# IOTBeev0_1.net
KiCad netlist of a schematic drawn in EAGLE
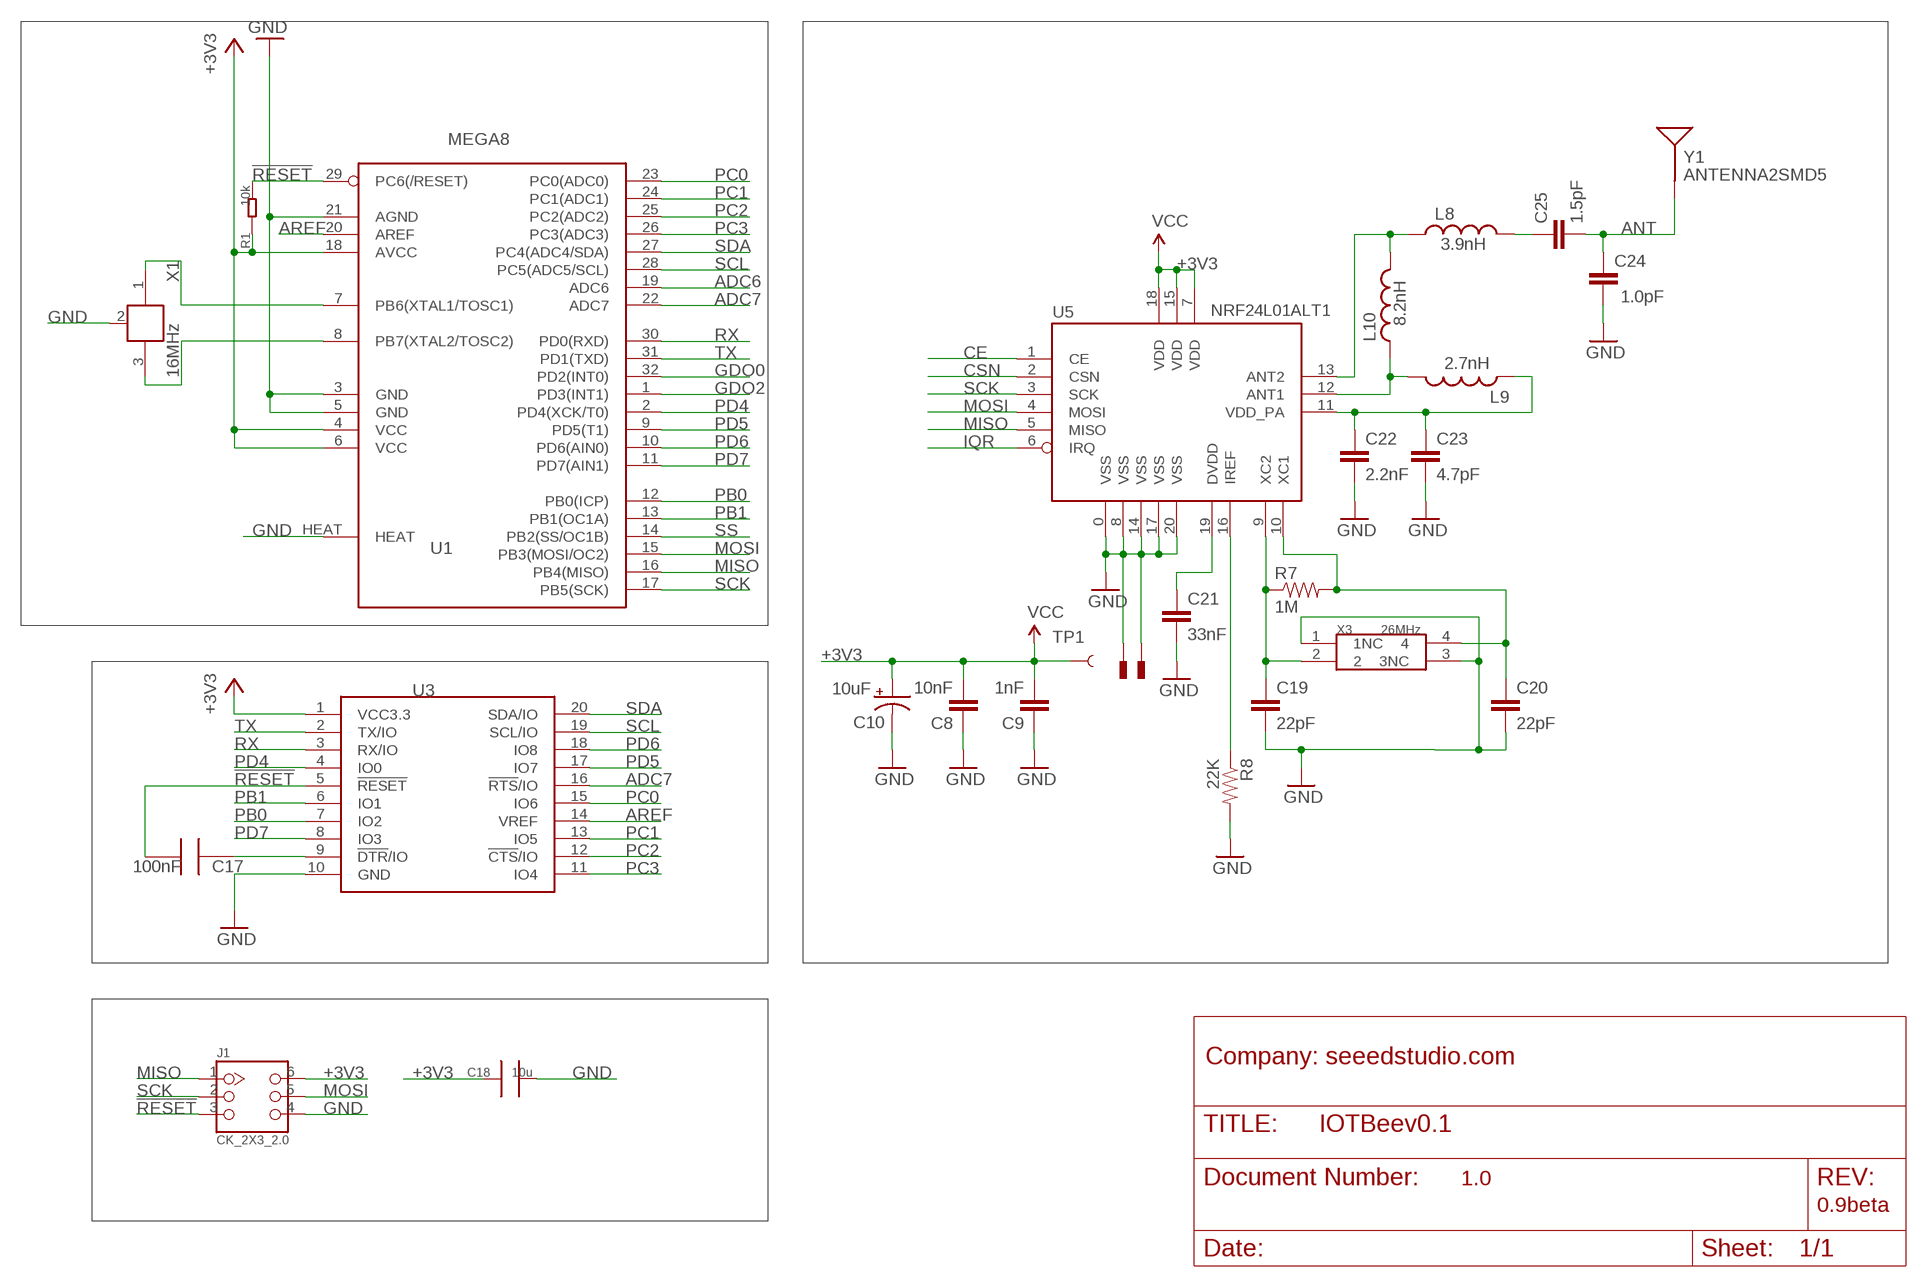
[diagram p0: schematic, sheet 1]

(export (version "E")
  (design (tool "Eeschema 10.0.6"))
  (components
    (comp (ref "C8")
      (value "10nF")
      (footprint "eagle-import:0402-CAP")
      (libsource (lib "eagle-import") (part "CAP0402-CAP"))
    )
    (comp (ref "C9")
      (value "1nF")
      (footprint "eagle-import:0402-CAP")
      (libsource (lib "eagle-import") (part "CAP0402-CAP"))
    )
    (comp (ref "C10")
      (value "10uF")
      (footprint "eagle-import:EIA3528")
      (libsource (lib "eagle-import") (part "CAP_POL3528"))
    )
    (comp (ref "C17")
      (value "100nF")
      (footprint "eagle-import:0603_S")
      (libsource (lib "eagle-import") (part "C0603_S"))
    )
    (comp (ref "C18")
      (value "10u")
      (footprint "eagle-import:0805")
      (libsource (lib "eagle-import") (part "C0805"))
    )
    (comp (ref "C19")
      (value "22pF")
      (footprint "eagle-import:0402-CAP")
      (libsource (lib "eagle-import") (part "CAP0402-CAP"))
    )
    (comp (ref "C20")
      (value "22pF")
      (footprint "eagle-import:0402-CAP")
      (libsource (lib "eagle-import") (part "CAP0402-CAP"))
    )
    (comp (ref "C21")
      (value "33nF")
      (footprint "eagle-import:0402-CAP")
      (libsource (lib "eagle-import") (part "CAP0402-CAP"))
    )
    (comp (ref "C22")
      (value "2.2nF")
      (footprint "eagle-import:0402-CAP")
      (libsource (lib "eagle-import") (part "CAP0402-CAP"))
    )
    (comp (ref "C23")
      (value "4.7pF")
      (footprint "eagle-import:0402-CAP")
      (libsource (lib "eagle-import") (part "CAP0402-CAP"))
    )
    (comp (ref "C24")
      (value "1.0pF")
      (footprint "eagle-import:0402-CAP")
      (libsource (lib "eagle-import") (part "CAP0402-CAP"))
    )
    (comp (ref "C25")
      (value "1.5pF")
      (footprint "eagle-import:0402-CAP")
      (libsource (lib "eagle-import") (part "CAP0402-CAP"))
    )
    (comp (ref "J1")
      (value "CK_2X3_2.0")
      (footprint "eagle-import:CK_2X3_2.0")
      (libsource (lib "eagle-import") (part "CK_2X3_2.0"))
    )
    (comp (ref "L8")
      (value "3.9nH")
      (footprint "eagle-import:C0402")
      (libsource (lib "eagle-import") (part "INDUCTOR0402"))
    )
    (comp (ref "L9")
      (value "2.7nH")
      (footprint "eagle-import:C0402")
      (libsource (lib "eagle-import") (part "INDUCTOR0402"))
    )
    (comp (ref "L10")
      (value "8.2nH")
      (footprint "eagle-import:C0402")
      (libsource (lib "eagle-import") (part "INDUCTOR0402"))
    )
    (comp (ref "R1")
      (value "10k")
      (footprint "eagle-import:0603_S")
      (libsource (lib "eagle-import") (part "R0603_S"))
    )
    (comp (ref "R7")
      (value "1M")
      (footprint "eagle-import:0402-RES")
      (libsource (lib "eagle-import") (part "RESISTOR0402-RES"))
    )
    (comp (ref "R8")
      (value "22K")
      (footprint "eagle-import:0402-RES")
      (libsource (lib "eagle-import") (part "RESISTOR0402-RES"))
    )
    (comp (ref "TP1")
      (value "TEST-POINT3X5")
      (footprint "eagle-import:PAD.03X.05")
      (libsource (lib "eagle-import") (part "TEST-POINT3X5"))
    )
    (comp (ref "U$2")
      (value "PAD")
      (footprint "eagle-import:PAD-0.008")
      (libsource (lib "eagle-import") (part "PAD"))
    )
    (comp (ref "U$4")
      (value "PAD")
      (footprint "eagle-import:PAD-0.008")
      (libsource (lib "eagle-import") (part "PAD"))
    )
    (comp (ref "U1")
      (value "MEGA8")
      (footprint "eagle-import:MLF32X")
      (libsource (lib "eagle-import") (part "MEGA8"))
    )
    (comp (ref "U3")
      (value "BEE-OPENBEE-BTSMD")
      (footprint "eagle-import:20P-SMD-2.0-BT")
      (libsource (lib "eagle-import") (part "BEE-OPENBEE-BTSMD"))
    )
    (comp (ref "U5")
      (value "NRF24L01ALT1")
      (footprint "eagle-import:QFN20_ALT1")
      (libsource (lib "eagle-import") (part "NRF24L01ALT1"))
    )
    (comp (ref "X1")
      (value "16MHz")
      (footprint "eagle-import:XTAL_3X2")
      (libsource (lib "eagle-import") (part "XTAL_NCVER"))
    )
    (comp (ref "X3")
      (value "26MHz")
      (footprint "eagle-import:X3225")
      (libsource (lib "eagle-import") (part "XTAL_SMD_3225"))
    )
    (comp (ref "Y1")
      (value "ANTENNA2SMD5")
      (footprint "eagle-import:ANTENNA-CHIP5")
      (libsource (lib "eagle-import") (part "ANTENNA2SMD5"))
    )
  )
  (nets
    (net (code "1") (name "+3V3") (class "Default")
      (node (ref "C10") (pin "A") (pinfunction "+_A") (pintype "passive"))
      (node (ref "C18") (pin "1") (pinfunction "1_1") (pintype "bidirectional"))
      (node (ref "C8") (pin "2") (pinfunction "2_2") (pintype "passive"))
      (node (ref "C9") (pin "2") (pinfunction "2_2") (pintype "passive"))
      (node (ref "J1") (pin "6") (pinfunction "P$6_6") (pintype "bidirectional"))
      (node (ref "R1") (pin "1") (pinfunction "1_1") (pintype "bidirectional"))
      (node (ref "TP1") (pin "P$1") (pinfunction "1_P$1") (pintype "bidirectional"))
      (node (ref "U1") (pin "18") (pinfunction "AVCC_18") (pintype "bidirectional"))
      (node (ref "U1") (pin "4") (pinfunction "VCC_4") (pintype "bidirectional"))
      (node (ref "U1") (pin "6") (pinfunction "VCC_6") (pintype "bidirectional"))
      (node (ref "U3") (pin "1") (pinfunction "VCC3.3_1") (pintype "bidirectional"))
      (node (ref "U5") (pin "15") (pinfunction "VDD_15") (pintype "power_in"))
      (node (ref "U5") (pin "18") (pinfunction "VDD_18") (pintype "power_in"))
      (node (ref "U5") (pin "7") (pinfunction "VDD_7") (pintype "power_in"))
    )
    (net (code "2") (name "/ADC6") (class "Default")
      (node (ref "U1") (pin "19") (pinfunction "ADC6_19") (pintype "bidirectional"))
    )
    (net (code "3") (name "/ADC7") (class "Default")
      (node (ref "U1") (pin "22") (pinfunction "ADC7_22") (pintype "bidirectional"))
      (node (ref "U3") (pin "16") (pinfunction "~{RTS}/IO_16") (pintype "bidirectional"))
    )
    (net (code "4") (name "/ANT") (class "Default")
      (node (ref "C24") (pin "2") (pinfunction "2_2") (pintype "passive"))
      (node (ref "C25") (pin "2") (pinfunction "2_2") (pintype "passive"))
      (node (ref "Y1") (pin "FEED") (pinfunction "SIGNAL_FEED") (pintype "bidirectional"))
    )
    (net (code "5") (name "/AREF") (class "Default")
      (node (ref "U1") (pin "20") (pinfunction "AREF_20") (pintype "bidirectional"))
      (node (ref "U3") (pin "14") (pinfunction "VREF_14") (pintype "bidirectional"))
    )
    (net (code "6") (name "/CE") (class "Default")
      (node (ref "U5") (pin "1") (pinfunction "CE_1") (pintype "input"))
    )
    (net (code "7") (name "/CSN") (class "Default")
      (node (ref "U5") (pin "2") (pinfunction "CSN_2") (pintype "input"))
    )
    (net (code "8") (name "/GDO0") (class "Default")
      (node (ref "U1") (pin "32") (pinfunction "PD2(INT0)_32") (pintype "bidirectional"))
    )
    (net (code "9") (name "/GDO2") (class "Default")
      (node (ref "U1") (pin "1") (pinfunction "PD3(INT1)_1") (pintype "bidirectional"))
    )
    (net (code "10") (name "/IQR") (class "Default")
      (node (ref "U5") (pin "6") (pinfunction "IRQ_6") (pintype "output"))
    )
    (net (code "11") (name "/MISO") (class "Default")
      (node (ref "J1") (pin "1") (pinfunction "P$1_1") (pintype "bidirectional"))
      (node (ref "U1") (pin "16") (pinfunction "PB4(MISO)_16") (pintype "bidirectional"))
      (node (ref "U5") (pin "5") (pinfunction "MISO_5") (pintype "output"))
    )
    (net (code "12") (name "/MOSI") (class "Default")
      (node (ref "J1") (pin "5") (pinfunction "P$5_5") (pintype "bidirectional"))
      (node (ref "U1") (pin "15") (pinfunction "PB3(MOSI/OC2)_15") (pintype "bidirectional"))
      (node (ref "U5") (pin "4") (pinfunction "MOSI_4") (pintype "input"))
    )
    (net (code "13") (name "/PB0") (class "Default")
      (node (ref "U1") (pin "12") (pinfunction "PB0(ICP)_12") (pintype "bidirectional"))
      (node (ref "U3") (pin "7") (pinfunction "IO2_7") (pintype "bidirectional"))
    )
    (net (code "14") (name "/PB1") (class "Default")
      (node (ref "U1") (pin "13") (pinfunction "PB1(OC1A)_13") (pintype "bidirectional"))
      (node (ref "U3") (pin "6") (pinfunction "IO1_6") (pintype "bidirectional"))
    )
    (net (code "15") (name "/PC0") (class "Default")
      (node (ref "U1") (pin "23") (pinfunction "PC0(ADC0)_23") (pintype "bidirectional"))
      (node (ref "U3") (pin "15") (pinfunction "IO6_15") (pintype "bidirectional"))
    )
    (net (code "16") (name "/PC1") (class "Default")
      (node (ref "U1") (pin "24") (pinfunction "PC1(ADC1)_24") (pintype "bidirectional"))
      (node (ref "U3") (pin "13") (pinfunction "IO5_13") (pintype "bidirectional"))
    )
    (net (code "17") (name "/PC2") (class "Default")
      (node (ref "U1") (pin "25") (pinfunction "PC2(ADC2)_25") (pintype "bidirectional"))
      (node (ref "U3") (pin "12") (pinfunction "~{CTS}/IO_12") (pintype "bidirectional"))
    )
    (net (code "18") (name "/PC3") (class "Default")
      (node (ref "U1") (pin "26") (pinfunction "PC3(ADC3)_26") (pintype "bidirectional"))
      (node (ref "U3") (pin "11") (pinfunction "IO4_11") (pintype "bidirectional"))
    )
    (net (code "19") (name "/PD4") (class "Default")
      (node (ref "U1") (pin "2") (pinfunction "PD4(XCK/T0)_2") (pintype "bidirectional"))
      (node (ref "U3") (pin "4") (pinfunction "IO0_4") (pintype "bidirectional"))
    )
    (net (code "20") (name "/PD5") (class "Default")
      (node (ref "U1") (pin "9") (pinfunction "PD5(T1)_9") (pintype "bidirectional"))
      (node (ref "U3") (pin "17") (pinfunction "IO7_17") (pintype "bidirectional"))
    )
    (net (code "21") (name "/PD6") (class "Default")
      (node (ref "U1") (pin "10") (pinfunction "PD6(AIN0)_10") (pintype "bidirectional"))
      (node (ref "U3") (pin "18") (pinfunction "IO8_18") (pintype "bidirectional"))
    )
    (net (code "22") (name "/PD7") (class "Default")
      (node (ref "U1") (pin "11") (pinfunction "PD7(AIN1)_11") (pintype "bidirectional"))
      (node (ref "U3") (pin "8") (pinfunction "IO3_8") (pintype "bidirectional"))
    )
    (net (code "23") (name "/RX") (class "Default")
      (node (ref "U1") (pin "30") (pinfunction "PD0(RXD)_30") (pintype "bidirectional"))
      (node (ref "U3") (pin "3") (pinfunction "RX/IO_3") (pintype "bidirectional"))
    )
    (net (code "24") (name "/SCK") (class "Default")
      (node (ref "J1") (pin "2") (pinfunction "P$2_2") (pintype "bidirectional"))
      (node (ref "U1") (pin "17") (pinfunction "PB5(SCK)_17") (pintype "bidirectional"))
      (node (ref "U5") (pin "3") (pinfunction "SCK_3") (pintype "input"))
    )
    (net (code "25") (name "/SCL") (class "Default")
      (node (ref "U1") (pin "28") (pinfunction "PC5(ADC5/SCL)_28") (pintype "bidirectional"))
      (node (ref "U3") (pin "19") (pinfunction "SCL/IO_19") (pintype "bidirectional"))
    )
    (net (code "26") (name "/SDA") (class "Default")
      (node (ref "U1") (pin "27") (pinfunction "PC4(ADC4/SDA)_27") (pintype "bidirectional"))
      (node (ref "U3") (pin "20") (pinfunction "SDA/IO_20") (pintype "bidirectional"))
    )
    (net (code "27") (name "/SS") (class "Default")
      (node (ref "U1") (pin "14") (pinfunction "PB2(SS/OC1B)_14") (pintype "bidirectional"))
    )
    (net (code "28") (name "/TX") (class "Default")
      (node (ref "U1") (pin "31") (pinfunction "PD1(TXD)_31") (pintype "bidirectional"))
      (node (ref "U3") (pin "2") (pinfunction "TX/IO_2") (pintype "bidirectional"))
    )
    (net (code "29") (name "/~{RESET}") (class "Default")
      (node (ref "C17") (pin "2") (pinfunction "2_2") (pintype "bidirectional"))
      (node (ref "J1") (pin "3") (pinfunction "P$3_3") (pintype "bidirectional"))
      (node (ref "R1") (pin "2") (pinfunction "2_2") (pintype "bidirectional"))
      (node (ref "U1") (pin "29") (pinfunction "PC6(/RESET)_29") (pintype "bidirectional"))
      (node (ref "U3") (pin "5") (pinfunction "~{RESET}_5") (pintype "bidirectional"))
    )
    (net (code "30") (name "GND") (class "Default")
      (node (ref "C10") (pin "C") (pinfunction "-_C") (pintype "passive"))
      (node (ref "C18") (pin "2") (pinfunction "2_2") (pintype "bidirectional"))
      (node (ref "C19") (pin "2") (pinfunction "2_2") (pintype "passive"))
      (node (ref "C20") (pin "2") (pinfunction "2_2") (pintype "passive"))
      (node (ref "C21") (pin "2") (pinfunction "2_2") (pintype "passive"))
      (node (ref "C22") (pin "2") (pinfunction "2_2") (pintype "passive"))
      (node (ref "C23") (pin "2") (pinfunction "2_2") (pintype "passive"))
      (node (ref "C24") (pin "1") (pinfunction "1_1") (pintype "passive"))
      (node (ref "C8") (pin "1") (pinfunction "1_1") (pintype "passive"))
      (node (ref "C9") (pin "1") (pinfunction "1_1") (pintype "passive"))
      (node (ref "J1") (pin "4") (pinfunction "P$4_4") (pintype "bidirectional"))
      (node (ref "R8") (pin "2") (pinfunction "2_2") (pintype "passive"))
      (node (ref "U$2") (pin "P$1") (pinfunction "P$1_P$1") (pintype "bidirectional"))
      (node (ref "U$4") (pin "P$1") (pinfunction "P$1_P$1") (pintype "bidirectional"))
      (node (ref "U1") (pin "21") (pinfunction "AGND_21") (pintype "bidirectional"))
      (node (ref "U1") (pin "3") (pinfunction "GND_3") (pintype "bidirectional"))
      (node (ref "U1") (pin "5") (pinfunction "GND_5") (pintype "bidirectional"))
      (node (ref "U1") (pin "HEAT") (pinfunction "HEAT_HEAT") (pintype "bidirectional"))
      (node (ref "U3") (pin "10") (pinfunction "GND_10") (pintype "bidirectional"))
      (node (ref "U5") (pin "0") (pinfunction "VSS_0") (pintype "power_in"))
      (node (ref "U5") (pin "14") (pinfunction "VSS_14") (pintype "power_in"))
      (node (ref "U5") (pin "17") (pinfunction "VSS_17") (pintype "power_in"))
      (node (ref "U5") (pin "20") (pinfunction "VSS_20") (pintype "power_in"))
      (node (ref "U5") (pin "8") (pinfunction "VSS_8") (pintype "power_in"))
      (node (ref "X1") (pin "2") (pinfunction "GND_2") (pintype "bidirectional"))
      (node (ref "X3") (pin "1") (pinfunction "1NC_1") (pintype "bidirectional"))
      (node (ref "X3") (pin "3") (pinfunction "3NC_3") (pintype "bidirectional"))
    )
    (net (code "31") (name "Net-(C25-Pad1)") (class "Default")
      (node (ref "C25") (pin "1") (pinfunction "1_1") (pintype "passive"))
      (node (ref "L8") (pin "2") (pinfunction "2_2") (pintype "passive"))
    )
    (net (code "32") (name "Net-(U1-PB6(XTAL1{slash}TOSC1))") (class "Default")
      (node (ref "U1") (pin "7") (pinfunction "PB6(XTAL1/TOSC1)_7") (pintype "bidirectional"))
      (node (ref "X1") (pin "1") (pinfunction "1_1") (pintype "bidirectional"))
    )
    (net (code "33") (name "Net-(U1-PB7(XTAL2{slash}TOSC2))") (class "Default")
      (node (ref "U1") (pin "8") (pinfunction "PB7(XTAL2/TOSC2)_8") (pintype "bidirectional"))
      (node (ref "X1") (pin "3") (pinfunction "2_3") (pintype "bidirectional"))
    )
    (net (code "34") (name "Net-(U3-~{DTR}{slash}IO)") (class "Default")
      (node (ref "C17") (pin "1") (pinfunction "1_1") (pintype "bidirectional"))
      (node (ref "U3") (pin "9") (pinfunction "~{DTR}/IO_9") (pintype "bidirectional"))
    )
    (net (code "35") (name "Net-(U5-ANT1)") (class "Default")
      (node (ref "L10") (pin "1") (pinfunction "1_1") (pintype "passive"))
      (node (ref "L9") (pin "2") (pinfunction "2_2") (pintype "passive"))
      (node (ref "U5") (pin "12") (pinfunction "ANT1_12") (pintype "output"))
    )
    (net (code "36") (name "Net-(U5-ANT2)") (class "Default")
      (node (ref "L10") (pin "2") (pinfunction "2_2") (pintype "passive"))
      (node (ref "L8") (pin "1") (pinfunction "1_1") (pintype "passive"))
      (node (ref "U5") (pin "13") (pinfunction "ANT2_13") (pintype "output"))
    )
    (net (code "37") (name "Net-(U5-DVDD)") (class "Default")
      (node (ref "C21") (pin "1") (pinfunction "1_1") (pintype "passive"))
      (node (ref "U5") (pin "19") (pinfunction "DVDD_19") (pintype "power_in"))
    )
    (net (code "38") (name "Net-(U5-IREF)") (class "Default")
      (node (ref "R8") (pin "1") (pinfunction "1_1") (pintype "passive"))
      (node (ref "U5") (pin "16") (pinfunction "IREF_16") (pintype "input"))
    )
    (net (code "39") (name "Net-(U5-VDD_PA)") (class "Default")
      (node (ref "C22") (pin "1") (pinfunction "1_1") (pintype "passive"))
      (node (ref "C23") (pin "1") (pinfunction "1_1") (pintype "passive"))
      (node (ref "L9") (pin "1") (pinfunction "1_1") (pintype "passive"))
      (node (ref "U5") (pin "11") (pinfunction "VDD_PA_11") (pintype "power_in"))
    )
    (net (code "40") (name "Net-(U5-XC1)") (class "Default")
      (node (ref "C20") (pin "1") (pinfunction "1_1") (pintype "passive"))
      (node (ref "R7") (pin "2") (pinfunction "2_2") (pintype "passive"))
      (node (ref "U5") (pin "10") (pinfunction "XC1_10") (pintype "input"))
      (node (ref "X3") (pin "4") (pinfunction "4_4") (pintype "bidirectional"))
    )
    (net (code "41") (name "Net-(U5-XC2)") (class "Default")
      (node (ref "C19") (pin "1") (pinfunction "1_1") (pintype "passive"))
      (node (ref "R7") (pin "1") (pinfunction "1_1") (pintype "passive"))
      (node (ref "U5") (pin "9") (pinfunction "XC2_9") (pintype "input"))
      (node (ref "X3") (pin "2") (pinfunction "2_2") (pintype "bidirectional"))
    )
  )
)
